# FT231X_BRK.net
KiCad netlist of a schematic drawn in Altium Designer
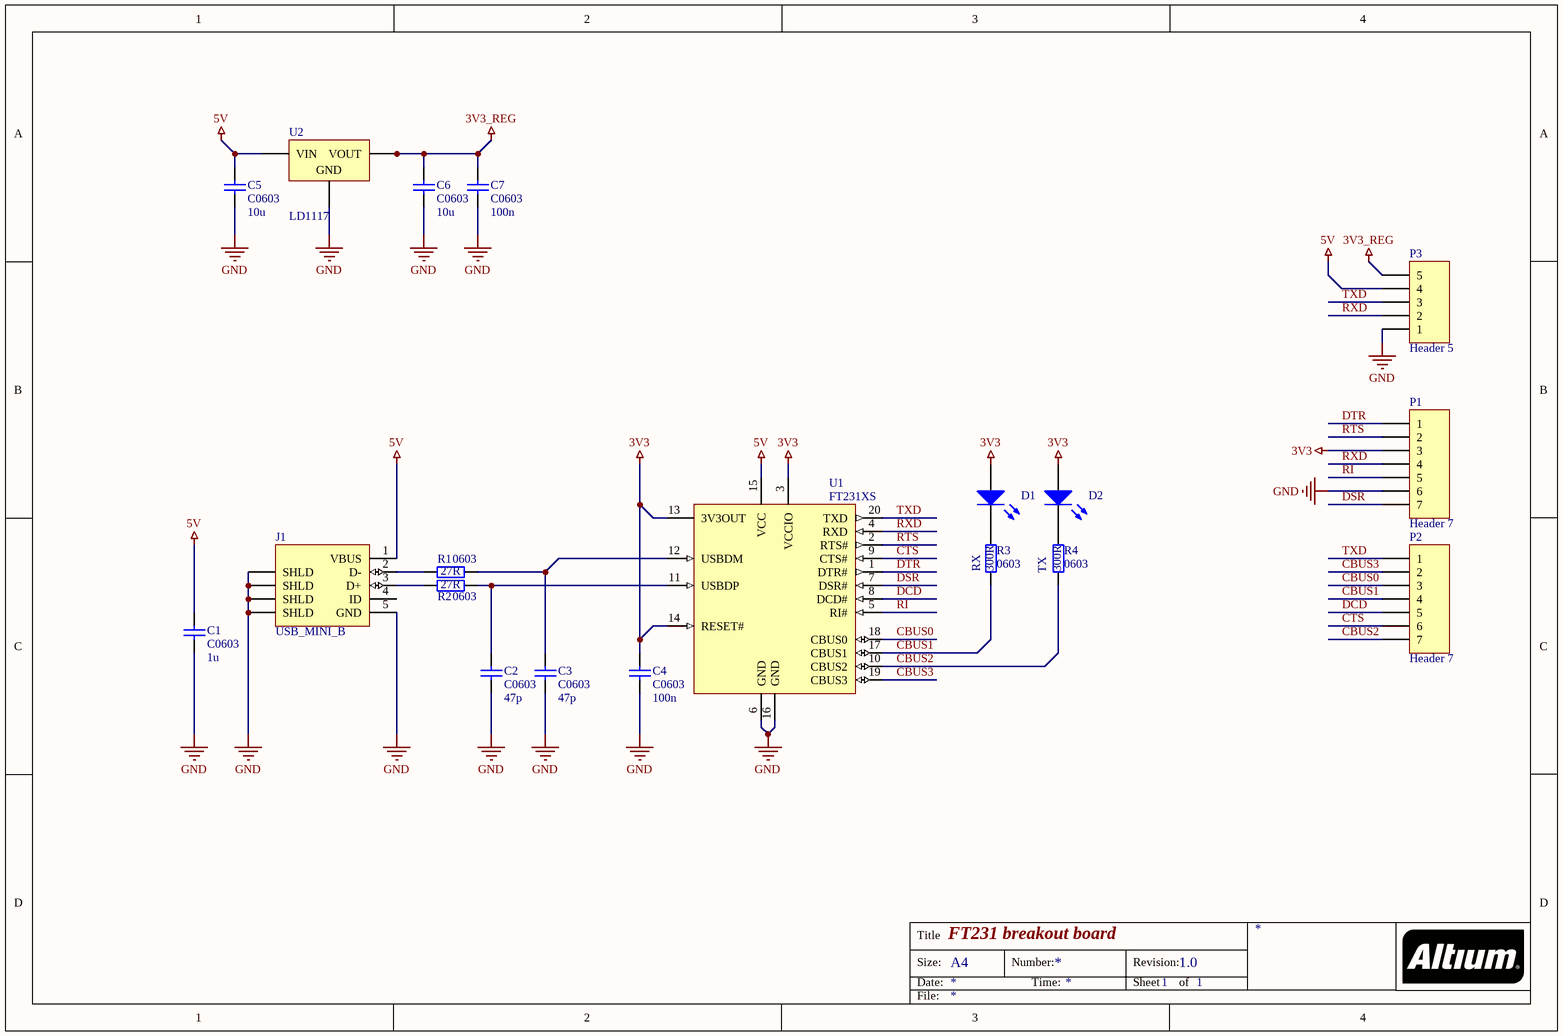
[diagram p0: FT231X_BRK.SchDoc]

(export (version "E")
  (design (tool "Eeschema 10.0.6"))
  (components
    (comp (ref "C1")
      (value "1u")
      (footprint "C0603")
      (description "Generic capacitor")
      (libsource (lib "_RLC") (part "Cap"))
    )
    (comp (ref "C2")
      (value "47p")
      (footprint "C0603")
      (description "Generic capacitor")
      (libsource (lib "_RLC") (part "Cap"))
    )
    (comp (ref "C3")
      (value "47p")
      (footprint "C0603")
      (description "Generic capacitor")
      (libsource (lib "_RLC") (part "Cap"))
    )
    (comp (ref "C4")
      (value "100n")
      (footprint "C0603")
      (description "Generic capacitor")
      (libsource (lib "_RLC") (part "Cap"))
    )
    (comp (ref "C5")
      (value "10u")
      (footprint "C0603")
      (description "Generic capacitor")
      (libsource (lib "_RLC") (part "Cap"))
    )
    (comp (ref "C6")
      (value "10u")
      (footprint "C0603")
      (description "Generic capacitor")
      (libsource (lib "_RLC") (part "Cap"))
    )
    (comp (ref "C7")
      (value "100n")
      (footprint "C0603")
      (description "Generic capacitor")
      (libsource (lib "_RLC") (part "Cap"))
    )
    (comp (ref "D1")
      (value "LEDX")
      (footprint "LED 0805 Blue")
      (description "Typical LED")
      (libsource (lib "_Diodes") (part "LEDX"))
    )
    (comp (ref "D2")
      (value "LEDX")
      (footprint "LED 0805 Blue")
      (description "Typical LED")
      (libsource (lib "_Diodes") (part "LEDX"))
    )
    (comp (ref "J1")
      (value "USB_MINI_B")
      (footprint "USB_Mini_B_9.3x7.7")
      (description "USB On-The-Go (OTG) Mini-B Receptacle")
      (libsource (lib "_Connectors") (part "USB_MINI_B2"))
    )
    (comp (ref "P1")
      (value "Header 7")
      (footprint "HEADER 1X7 MALE")
      (description "Header, 7-Pin")
      (fields (field (name "PUBLISHER") "Altium Limited"))
      (libsource (lib "_Connectors") (part "Header 7"))
    )
    (comp (ref "P2")
      (value "Header 7")
      (footprint "HEADER 1X7 MALE")
      (description "Header, 7-Pin")
      (fields (field (name "PUBLISHER") "Altium Limited"))
      (libsource (lib "_Connectors") (part "Header 7"))
    )
    (comp (ref "P3")
      (value "Header 5")
      (footprint "HEADER 1X5 MALE")
      (description "Header, 5-Pin")
      (fields (field (name "PUBLISHER") "Altium Limited"))
      (libsource (lib "_Connectors") (part "Header 5"))
    )
    (comp (ref "R1")
      (value "27R")
      (footprint "0603")
      (description "Generic resistor")
      (libsource (lib "_RLC") (part "Res"))
    )
    (comp (ref "R2")
      (value "27R")
      (footprint "0603")
      (description "Generic resistor")
      (libsource (lib "_RLC") (part "Res"))
    )
    (comp (ref "R3")
      (value "300R")
      (footprint "0603")
      (description "Generic resistor")
      (libsource (lib "") (part "Res_1"))
    )
    (comp (ref "R4")
      (value "300R")
      (footprint "0603")
      (description "Generic resistor")
      (libsource (lib "") (part "Res_1"))
    )
    (comp (ref "U1")
      (value "FT231XS")
      (footprint "SSOP20_M")
      (fields (field (name "MANUFACTURER") "FTDI") (field (name "PARTNUMBER") "FT231XS-U"))
      (libsource (lib "_Microcircuits") (part "FT231XS"))
    )
    (comp (ref "U2")
      (value "LD1117")
      (footprint "TO-252")
      (description "Low drop positive voltage regulator")
      (libsource (lib "_Microcircuits") (part "LD1117"))
    )
  )
  (nets
    (net (code "1") (name "/CBUS0") (class "Default")
      (node (ref "P2") (pin "3") (pinfunction "3_3") (pintype "passive"))
      (node (ref "U1") (pin "18") (pinfunction "CBUS0_18") (pintype "bidirectional"))
    )
    (net (code "2") (name "/CBUS1") (class "Default")
      (node (ref "P2") (pin "4") (pinfunction "4_4") (pintype "passive"))
      (node (ref "R3") (pin "2") (pinfunction "2_2") (pintype "passive"))
      (node (ref "U1") (pin "17") (pinfunction "CBUS1_17") (pintype "bidirectional"))
    )
    (net (code "3") (name "/CBUS2") (class "Default")
      (node (ref "P2") (pin "7") (pinfunction "7_7") (pintype "passive"))
      (node (ref "R4") (pin "2") (pinfunction "2_2") (pintype "passive"))
      (node (ref "U1") (pin "10") (pinfunction "CBUS2_10") (pintype "bidirectional"))
    )
    (net (code "4") (name "/CBUS3") (class "Default")
      (node (ref "P2") (pin "2") (pinfunction "2_2") (pintype "passive"))
      (node (ref "U1") (pin "19") (pinfunction "CBUS3_19") (pintype "bidirectional"))
    )
    (net (code "5") (name "/CTS") (class "Default")
      (node (ref "P2") (pin "6") (pinfunction "6_6") (pintype "passive"))
      (node (ref "U1") (pin "9") (pinfunction "CTS#_9") (pintype "input"))
    )
    (net (code "6") (name "/DCD") (class "Default")
      (node (ref "P2") (pin "5") (pinfunction "5_5") (pintype "passive"))
      (node (ref "U1") (pin "8") (pinfunction "DCD#_8") (pintype "input"))
    )
    (net (code "7") (name "/DSR") (class "Default")
      (node (ref "P1") (pin "7") (pinfunction "7_7") (pintype "passive"))
      (node (ref "U1") (pin "7") (pinfunction "DSR#_7") (pintype "input"))
    )
    (net (code "8") (name "/DTR") (class "Default")
      (node (ref "P1") (pin "1") (pinfunction "1_1") (pintype "passive"))
      (node (ref "U1") (pin "1") (pinfunction "DTR#_1") (pintype "output"))
    )
    (net (code "9") (name "/RI") (class "Default")
      (node (ref "P1") (pin "5") (pinfunction "5_5") (pintype "passive"))
      (node (ref "U1") (pin "5") (pinfunction "RI#_5") (pintype "input"))
    )
    (net (code "10") (name "/RTS") (class "Default")
      (node (ref "P1") (pin "2") (pinfunction "2_2") (pintype "passive"))
      (node (ref "U1") (pin "2") (pinfunction "RTS#_2") (pintype "output"))
    )
    (net (code "11") (name "/RXD") (class "Default")
      (node (ref "P1") (pin "4") (pinfunction "4_4") (pintype "passive"))
      (node (ref "P3") (pin "2") (pinfunction "2_2") (pintype "passive"))
      (node (ref "U1") (pin "4") (pinfunction "RXD_4") (pintype "input"))
    )
    (net (code "12") (name "/TXD") (class "Default")
      (node (ref "P2") (pin "1") (pinfunction "1_1") (pintype "passive"))
      (node (ref "P3") (pin "3") (pinfunction "3_3") (pintype "passive"))
      (node (ref "U1") (pin "20") (pinfunction "TXD_20") (pintype "output"))
    )
    (net (code "13") (name "3V3") (class "Default")
      (node (ref "C4") (pin "1") (pinfunction "1_1") (pintype "passive"))
      (node (ref "D1") (pin "1") (pinfunction "A_1") (pintype "passive"))
      (node (ref "D2") (pin "1") (pinfunction "A_1") (pintype "passive"))
      (node (ref "P1") (pin "3") (pinfunction "3_3") (pintype "passive"))
      (node (ref "U1") (pin "13") (pinfunction "3V3OUT_13") (pintype "power_in"))
      (node (ref "U1") (pin "14") (pinfunction "RESET#_14") (pintype "input"))
      (node (ref "U1") (pin "3") (pinfunction "VCCIO_3") (pintype "power_in"))
    )
    (net (code "14") (name "3V3_REG") (class "Default")
      (node (ref "C6") (pin "1") (pinfunction "1_1") (pintype "passive"))
      (node (ref "C7") (pin "1") (pinfunction "1_1") (pintype "passive"))
      (node (ref "P3") (pin "5") (pinfunction "5_5") (pintype "passive"))
      (node (ref "U2") (pin "2") (pinfunction "VOUT_2") (pintype "power_in"))
      (node (ref "U2") (pin "4") (pinfunction "VOUT_4") (pintype "power_in"))
      (node (ref "U2") (pin "5") (pinfunction "VOUT_5") (pintype "power_in"))
      (node (ref "U2") (pin "6") (pinfunction "VOUT_6") (pintype "power_in"))
    )
    (net (code "15") (name "5V") (class "Default")
      (node (ref "C1") (pin "1") (pinfunction "1_1") (pintype "passive"))
      (node (ref "C5") (pin "1") (pinfunction "1_1") (pintype "passive"))
      (node (ref "J1") (pin "1") (pinfunction "VBUS_1") (pintype "power_in"))
      (node (ref "P3") (pin "4") (pinfunction "4_4") (pintype "passive"))
      (node (ref "U1") (pin "15") (pinfunction "VCC_15") (pintype "power_in"))
      (node (ref "U2") (pin "3") (pinfunction "VIN_3") (pintype "power_in"))
    )
    (net (code "16") (name "GND") (class "Default")
      (node (ref "C1") (pin "2") (pinfunction "2_2") (pintype "passive"))
      (node (ref "C2") (pin "2") (pinfunction "2_2") (pintype "passive"))
      (node (ref "C3") (pin "2") (pinfunction "2_2") (pintype "passive"))
      (node (ref "C4") (pin "2") (pinfunction "2_2") (pintype "passive"))
      (node (ref "C5") (pin "2") (pinfunction "2_2") (pintype "passive"))
      (node (ref "C6") (pin "2") (pinfunction "2_2") (pintype "passive"))
      (node (ref "C7") (pin "2") (pinfunction "2_2") (pintype "passive"))
      (node (ref "J1") (pin "5") (pinfunction "GND_5") (pintype "power_in"))
      (node (ref "J1") (pin "MH1") (pinfunction "SHLD_MH1") (pintype "passive"))
      (node (ref "J1") (pin "MH2") (pinfunction "SHLD_MH2") (pintype "passive"))
      (node (ref "J1") (pin "MH3") (pinfunction "SHLD_MH3") (pintype "passive"))
      (node (ref "J1") (pin "MH4") (pinfunction "SHLD_MH4") (pintype "passive"))
      (node (ref "P1") (pin "6") (pinfunction "6_6") (pintype "passive"))
      (node (ref "P3") (pin "1") (pinfunction "1_1") (pintype "passive"))
      (node (ref "U1") (pin "16") (pinfunction "GND_16") (pintype "power_in"))
      (node (ref "U1") (pin "6") (pinfunction "GND_6") (pintype "power_in"))
      (node (ref "U2") (pin "1") (pinfunction "GND_1") (pintype "power_in"))
    )
    (net (code "17") (name "Net-(D1-K)") (class "Default")
      (node (ref "D1") (pin "2") (pinfunction "K_2") (pintype "passive"))
      (node (ref "R3") (pin "1") (pinfunction "1_1") (pintype "passive"))
    )
    (net (code "18") (name "Net-(D2-K)") (class "Default")
      (node (ref "D2") (pin "2") (pinfunction "K_2") (pintype "passive"))
      (node (ref "R4") (pin "1") (pinfunction "1_1") (pintype "passive"))
    )
    (net (code "19") (name "Net-(J1-D+)") (class "Default")
      (node (ref "J1") (pin "3") (pinfunction "D+_3") (pintype "bidirectional"))
      (node (ref "R2") (pin "1") (pinfunction "1_1") (pintype "passive"))
    )
    (net (code "20") (name "Net-(J1-D-)") (class "Default")
      (node (ref "J1") (pin "2") (pinfunction "D-_2") (pintype "bidirectional"))
      (node (ref "R1") (pin "1") (pinfunction "1_1") (pintype "passive"))
    )
    (net (code "21") (name "Net-(U1-USBDM)") (class "Default")
      (node (ref "C3") (pin "1") (pinfunction "1_1") (pintype "passive"))
      (node (ref "R1") (pin "2") (pinfunction "2_2") (pintype "passive"))
      (node (ref "U1") (pin "12") (pinfunction "USBDM_12") (pintype "input"))
    )
    (net (code "22") (name "Net-(U1-USBDP)") (class "Default")
      (node (ref "C2") (pin "1") (pinfunction "1_1") (pintype "passive"))
      (node (ref "R2") (pin "2") (pinfunction "2_2") (pintype "passive"))
      (node (ref "U1") (pin "11") (pinfunction "USBDP_11") (pintype "input"))
    )
    (net (code "23") (name "unconnected-(J1-ID-Pad4)") (class "Default")
      (node (ref "J1") (pin "4") (pinfunction "ID_4") (pintype "passive"))
    )
  )
)
